# solar_collector_controller_V1_21.net
KiCad netlist of a schematic drawn in EAGLE
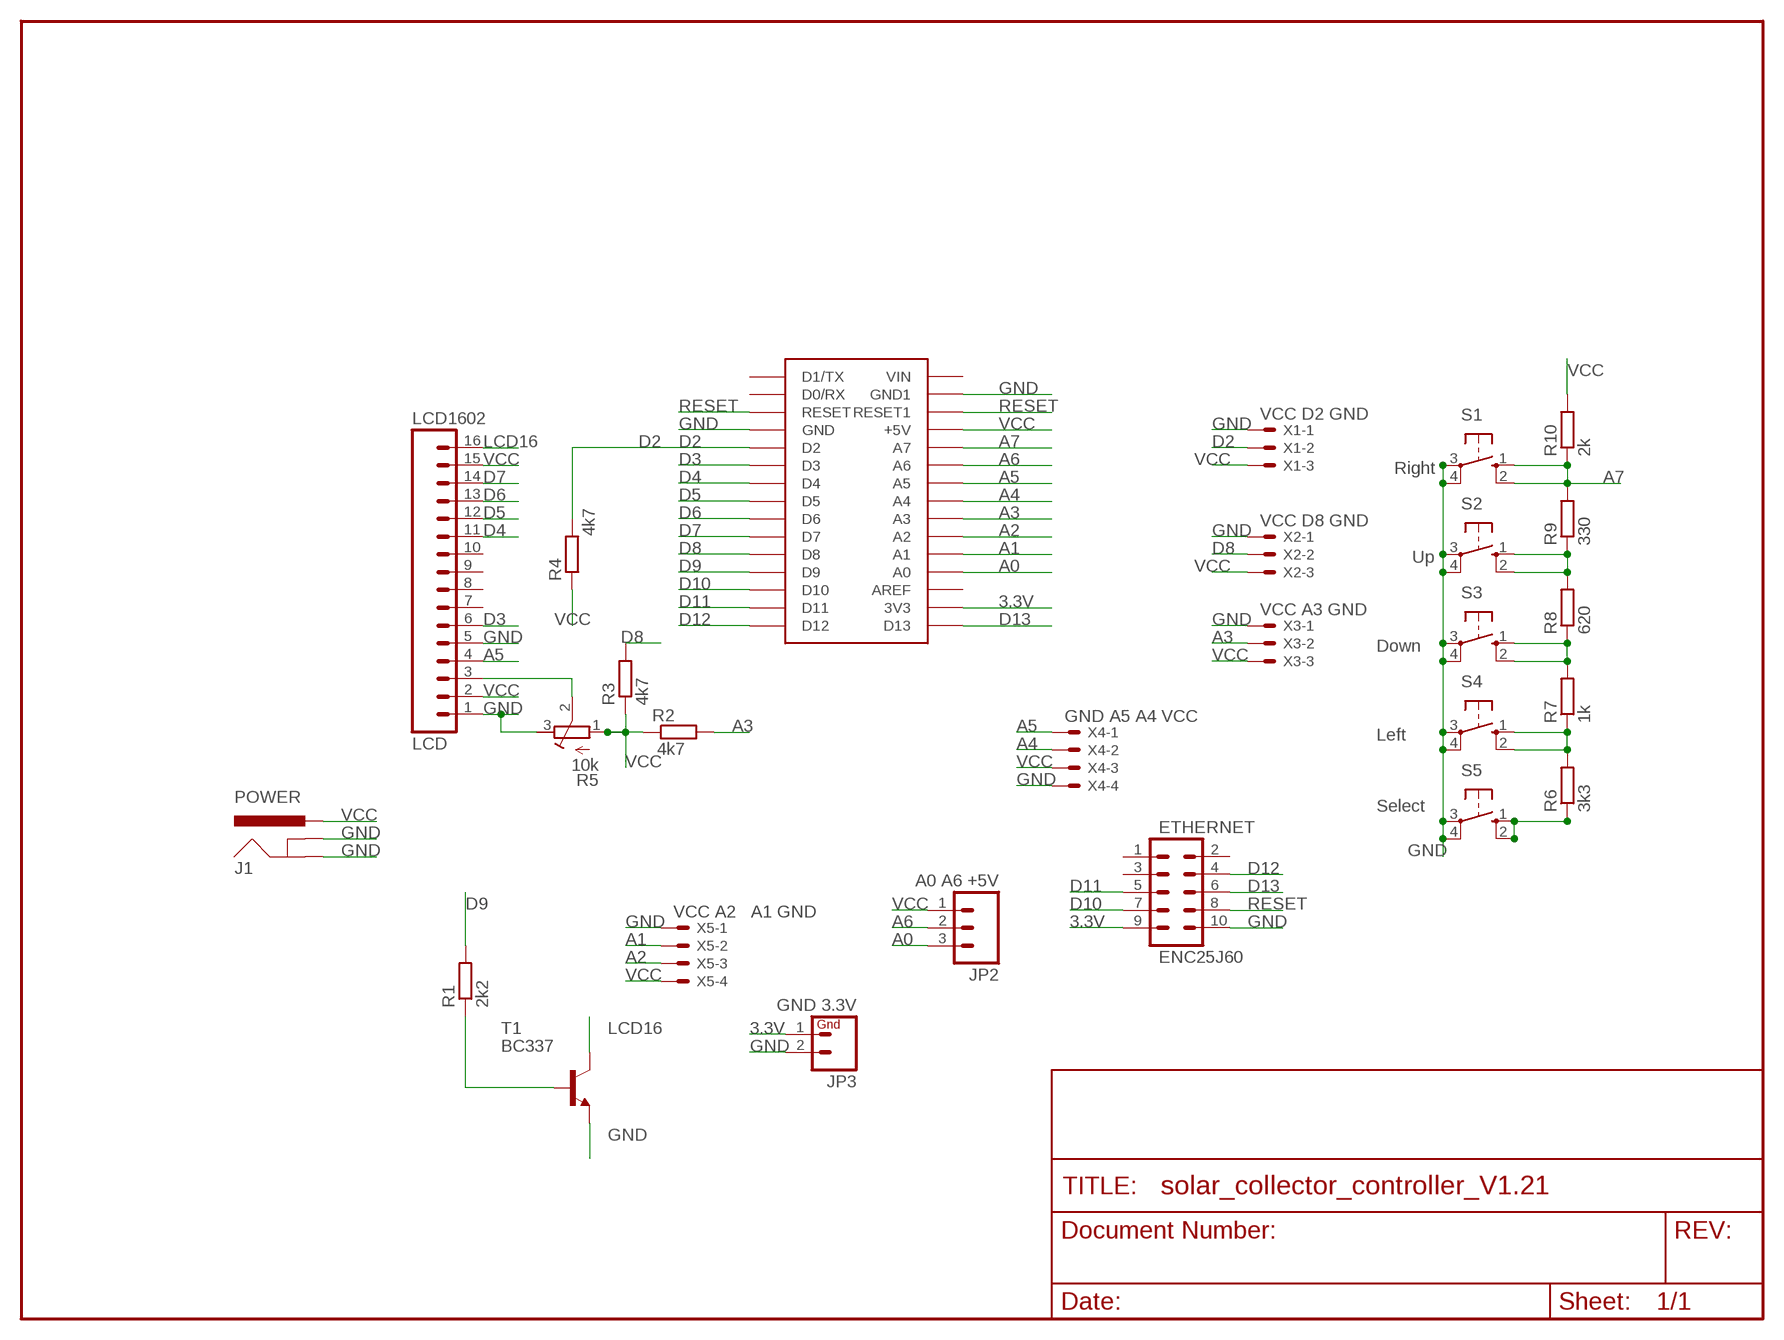
[diagram p0: schematic, sheet 1]

(export (version "E")
  (design (tool "Eeschema 10.0.6"))
  (components
    (comp (ref "ETHERNET")
      (value "ENC25J60")
      (footprint "eagle-import:AVR_ICSP")
      (libsource (lib "eagle-import") (part "M05X2PTH"))
    )
    (comp (ref "J1")
      (value "POWER")
      (footprint "eagle-import:POWER_JACK_PTH_LOCK")
      (libsource (lib "eagle-import") (part "POWER_JACKPTH_LOCK"))
    )
    (comp (ref "JP2")
      (value "A0 A6 +5V")
      (footprint "eagle-import:1X03")
      (libsource (lib "eagle-import") (part "M03PTH"))
    )
    (comp (ref "JP3")
      (value "GND 3.3V")
      (footprint "eagle-import:1X02")
      (libsource (lib "eagle-import") (part "M02PTH"))
    )
    (comp (ref "LCD1602")
      (value "LCD")
      (footprint "eagle-import:16P-2.54")
      (libsource (lib "eagle-import") (part "HEADER-16P-2.54"))
    )
    (comp (ref "R1")
      (value "2k2")
      (footprint "eagle-import:0207_10")
      (libsource (lib "eagle-import") (part "R-EU_0207/10"))
    )
    (comp (ref "R2")
      (value "4k7")
      (footprint "eagle-import:0207_10")
      (libsource (lib "eagle-import") (part "R-EU_0207/10"))
    )
    (comp (ref "R3")
      (value "4k7")
      (footprint "eagle-import:0207_10")
      (libsource (lib "eagle-import") (part "R-EU_0207/10"))
    )
    (comp (ref "R4")
      (value "4k7")
      (footprint "eagle-import:0207_10")
      (libsource (lib "eagle-import") (part "R-EU_0207/10"))
    )
    (comp (ref "R5")
      (value "10k")
      (footprint "eagle-import:RTRIM64W")
      (libsource (lib "eagle-import") (part "R-TRIMM64W"))
    )
    (comp (ref "R6")
      (value "3k3")
      (footprint "eagle-import:0207_10")
      (libsource (lib "eagle-import") (part "R-EU_0207/10"))
    )
    (comp (ref "R7")
      (value "1k")
      (footprint "eagle-import:0207_10")
      (libsource (lib "eagle-import") (part "R-EU_0207/10"))
    )
    (comp (ref "R8")
      (value "620")
      (footprint "eagle-import:0207_10")
      (libsource (lib "eagle-import") (part "R-EU_0207/10"))
    )
    (comp (ref "R9")
      (value "330")
      (footprint "eagle-import:0207_10")
      (libsource (lib "eagle-import") (part "R-EU_0207/10"))
    )
    (comp (ref "R10")
      (value "2k")
      (footprint "eagle-import:0207_10")
      (libsource (lib "eagle-import") (part "R-EU_0207/10"))
    )
    (comp (ref "S1")
      (value "Right")
      (footprint "eagle-import:B3F-10XX")
      (fields (field (name "MPN") "B3F-1000"))
      (libsource (lib "eagle-import") (part "10-XX"))
    )
    (comp (ref "S2")
      (value "Up")
      (footprint "eagle-import:B3F-10XX")
      (fields (field (name "MPN") "B3F-1000"))
      (libsource (lib "eagle-import") (part "10-XX"))
    )
    (comp (ref "S3")
      (value "Down")
      (footprint "eagle-import:B3F-10XX")
      (fields (field (name "MPN") "B3F-1000"))
      (libsource (lib "eagle-import") (part "10-XX"))
    )
    (comp (ref "S4")
      (value "Left")
      (footprint "eagle-import:B3F-10XX")
      (fields (field (name "MPN") "B3F-1000"))
      (libsource (lib "eagle-import") (part "10-XX"))
    )
    (comp (ref "S5")
      (value "Select")
      (footprint "eagle-import:B3F-10XX")
      (fields (field (name "MPN") "B3F-1000"))
      (libsource (lib "eagle-import") (part "10-XX"))
    )
    (comp (ref "T1")
      (value "BC337")
      (footprint "eagle-import:TO92")
      (libsource (lib "eagle-import") (part "BC337"))
    )
    (comp (ref "U$2")
      (value "ARDUINONANO")
      (footprint "eagle-import:PDIP-32")
      (libsource (lib "eagle-import") (part "ARDUINONANO"))
    )
    (comp (ref "X1")
      (value "VCC D2 GND")
      (footprint "eagle-import:22-23-2031")
      (fields (field (name "MF") "MOLEX") (field (name "MPN") "22-23-2031"))
      (libsource (lib "eagle-import") (part "22-23-2031"))
    )
    (comp (ref "X2")
      (value "VCC D8 GND")
      (footprint "eagle-import:22-23-2031")
      (fields (field (name "MF") "MOLEX") (field (name "MPN") "22-23-2031"))
      (libsource (lib "eagle-import") (part "22-23-2031"))
    )
    (comp (ref "X3")
      (value "VCC A3 GND")
      (footprint "eagle-import:22-23-2031")
      (fields (field (name "MF") "MOLEX") (field (name "MPN") "22-23-2031"))
      (libsource (lib "eagle-import") (part "22-23-2031"))
    )
    (comp (ref "X4")
      (value "GND A5 A4 VCC")
      (footprint "eagle-import:22-23-2041")
      (fields (field (name "MF") "MOLEX") (field (name "MPN") "22-23-2041"))
      (libsource (lib "eagle-import") (part "22-23-2041"))
    )
    (comp (ref "X5")
      (value "VCC A2 A1 GND")
      (footprint "eagle-import:22-23-2041")
      (fields (field (name "MF") "MOLEX") (field (name "MPN") "22-23-2041"))
      (libsource (lib "eagle-import") (part "22-23-2041"))
    )
  )
  (nets
    (net (code "1") (name "/3.3V") (class "Default")
      (node (ref "ETHERNET") (pin "9") (pinfunction "9_9") (pintype "passive"))
      (node (ref "JP3") (pin "1") (pinfunction "1_1") (pintype "passive"))
      (node (ref "U$2") (pin "3V3") (pinfunction "3V3_3V3") (pintype "bidirectional"))
    )
    (net (code "2") (name "/A0") (class "Default")
      (node (ref "JP2") (pin "3") (pinfunction "3_3") (pintype "passive"))
      (node (ref "U$2") (pin "A0") (pinfunction "A0_A0") (pintype "bidirectional"))
    )
    (net (code "3") (name "/A1") (class "Default")
      (node (ref "U$2") (pin "A1") (pinfunction "A1_A1") (pintype "bidirectional"))
      (node (ref "X5") (pin "2") (pinfunction "S_2") (pintype "passive"))
    )
    (net (code "4") (name "/A2") (class "Default")
      (node (ref "U$2") (pin "A2") (pinfunction "A2_A2") (pintype "bidirectional"))
      (node (ref "X5") (pin "3") (pinfunction "S_3") (pintype "passive"))
    )
    (net (code "5") (name "/A3") (class "Default")
      (node (ref "R2") (pin "2") (pinfunction "2_2") (pintype "passive"))
      (node (ref "U$2") (pin "A3") (pinfunction "A3_A3") (pintype "bidirectional"))
      (node (ref "X3") (pin "2") (pinfunction "S_2") (pintype "passive"))
    )
    (net (code "6") (name "/A4") (class "Default")
      (node (ref "U$2") (pin "A4") (pinfunction "A4_A4") (pintype "bidirectional"))
      (node (ref "X4") (pin "2") (pinfunction "S_2") (pintype "passive"))
    )
    (net (code "7") (name "/A5") (class "Default")
      (node (ref "LCD1602") (pin "4") (pinfunction "4_4") (pintype "passive"))
      (node (ref "U$2") (pin "A5") (pinfunction "A5_A5") (pintype "bidirectional"))
      (node (ref "X4") (pin "1") (pinfunction "S_1") (pintype "passive"))
    )
    (net (code "8") (name "/A6") (class "Default")
      (node (ref "JP2") (pin "2") (pinfunction "2_2") (pintype "passive"))
      (node (ref "U$2") (pin "A6") (pinfunction "A6_A6") (pintype "bidirectional"))
    )
    (net (code "9") (name "/A7") (class "Default")
      (node (ref "R10") (pin "1") (pinfunction "1_1") (pintype "passive"))
      (node (ref "R9") (pin "2") (pinfunction "2_2") (pintype "passive"))
      (node (ref "S1") (pin "1") (pinfunction "S_1") (pintype "passive"))
      (node (ref "S1") (pin "2") (pinfunction "S1_2") (pintype "passive"))
      (node (ref "U$2") (pin "A7") (pinfunction "A7_A7") (pintype "bidirectional"))
    )
    (net (code "10") (name "/D2") (class "Default")
      (node (ref "R4") (pin "2") (pinfunction "2_2") (pintype "passive"))
      (node (ref "U$2") (pin "D2") (pinfunction "D2_D2") (pintype "bidirectional"))
      (node (ref "X1") (pin "2") (pinfunction "S_2") (pintype "passive"))
    )
    (net (code "11") (name "/D3") (class "Default")
      (node (ref "LCD1602") (pin "6") (pinfunction "6_6") (pintype "passive"))
      (node (ref "U$2") (pin "D3") (pinfunction "D3_D3") (pintype "bidirectional"))
    )
    (net (code "12") (name "/D4") (class "Default")
      (node (ref "LCD1602") (pin "11") (pinfunction "11_11") (pintype "passive"))
      (node (ref "U$2") (pin "D4") (pinfunction "D4_D4") (pintype "bidirectional"))
    )
    (net (code "13") (name "/D5") (class "Default")
      (node (ref "LCD1602") (pin "12") (pinfunction "12_12") (pintype "passive"))
      (node (ref "U$2") (pin "D5") (pinfunction "D5_D5") (pintype "bidirectional"))
    )
    (net (code "14") (name "/D6") (class "Default")
      (node (ref "LCD1602") (pin "13") (pinfunction "13_13") (pintype "passive"))
      (node (ref "U$2") (pin "D6") (pinfunction "D6_D6") (pintype "bidirectional"))
    )
    (net (code "15") (name "/D7") (class "Default")
      (node (ref "LCD1602") (pin "14") (pinfunction "14_14") (pintype "passive"))
      (node (ref "U$2") (pin "D7") (pinfunction "D7_D7") (pintype "bidirectional"))
    )
    (net (code "16") (name "/D8") (class "Default")
      (node (ref "R3") (pin "2") (pinfunction "2_2") (pintype "passive"))
      (node (ref "U$2") (pin "D8") (pinfunction "D8_D8") (pintype "bidirectional"))
      (node (ref "X2") (pin "2") (pinfunction "S_2") (pintype "passive"))
    )
    (net (code "17") (name "/D9") (class "Default")
      (node (ref "R1") (pin "2") (pinfunction "2_2") (pintype "passive"))
      (node (ref "U$2") (pin "D9") (pinfunction "D9_D9") (pintype "bidirectional"))
    )
    (net (code "18") (name "/D10") (class "Default")
      (node (ref "ETHERNET") (pin "7") (pinfunction "7_7") (pintype "passive"))
      (node (ref "U$2") (pin "D10") (pinfunction "D10_D10") (pintype "bidirectional"))
    )
    (net (code "19") (name "/D11") (class "Default")
      (node (ref "ETHERNET") (pin "5") (pinfunction "5_5") (pintype "passive"))
      (node (ref "U$2") (pin "D11") (pinfunction "D11_D11") (pintype "bidirectional"))
    )
    (net (code "20") (name "/D12") (class "Default")
      (node (ref "ETHERNET") (pin "4") (pinfunction "4_4") (pintype "passive"))
      (node (ref "U$2") (pin "D12") (pinfunction "D12_D12") (pintype "bidirectional"))
    )
    (net (code "21") (name "/D13") (class "Default")
      (node (ref "ETHERNET") (pin "6") (pinfunction "6_6") (pintype "passive"))
      (node (ref "U$2") (pin "D13") (pinfunction "D13_D13") (pintype "bidirectional"))
    )
    (net (code "22") (name "/GND") (class "Default")
      (node (ref "ETHERNET") (pin "10") (pinfunction "10_10") (pintype "passive"))
      (node (ref "J1") (pin "GND") (pinfunction "GND_GND") (pintype "bidirectional"))
      (node (ref "J1") (pin "GNDBREAK") (pinfunction "GNDBREAK_GNDBREAK") (pintype "bidirectional"))
      (node (ref "JP3") (pin "2") (pinfunction "2_2") (pintype "passive"))
      (node (ref "LCD1602") (pin "1") (pinfunction "1_1") (pintype "passive"))
      (node (ref "LCD1602") (pin "5") (pinfunction "5_5") (pintype "passive"))
      (node (ref "R5") (pin "3") (pinfunction "A_3") (pintype "passive"))
      (node (ref "S1") (pin "3") (pinfunction "P_3") (pintype "passive"))
      (node (ref "S1") (pin "4") (pinfunction "P1_4") (pintype "passive"))
      (node (ref "S2") (pin "3") (pinfunction "P_3") (pintype "passive"))
      (node (ref "S2") (pin "4") (pinfunction "P1_4") (pintype "passive"))
      (node (ref "S3") (pin "3") (pinfunction "P_3") (pintype "passive"))
      (node (ref "S3") (pin "4") (pinfunction "P1_4") (pintype "passive"))
      (node (ref "S4") (pin "3") (pinfunction "P_3") (pintype "passive"))
      (node (ref "S4") (pin "4") (pinfunction "P1_4") (pintype "passive"))
      (node (ref "S5") (pin "3") (pinfunction "P_3") (pintype "passive"))
      (node (ref "S5") (pin "4") (pinfunction "P1_4") (pintype "passive"))
      (node (ref "T1") (pin "1") (pinfunction "E_1") (pintype "passive"))
      (node (ref "U$2") (pin "GND") (pinfunction "GND_GND") (pintype "bidirectional"))
      (node (ref "U$2") (pin "GND1") (pinfunction "GND1_GND1") (pintype "bidirectional"))
      (node (ref "X1") (pin "1") (pinfunction "S_1") (pintype "passive"))
      (node (ref "X2") (pin "1") (pinfunction "S_1") (pintype "passive"))
      (node (ref "X3") (pin "1") (pinfunction "S_1") (pintype "passive"))
      (node (ref "X4") (pin "4") (pinfunction "S_4") (pintype "passive"))
      (node (ref "X5") (pin "1") (pinfunction "S_1") (pintype "passive"))
    )
    (net (code "23") (name "/LCD16") (class "Default")
      (node (ref "LCD1602") (pin "16") (pinfunction "16_16") (pintype "passive"))
      (node (ref "T1") (pin "3") (pinfunction "C_3") (pintype "passive"))
    )
    (net (code "24") (name "/RESET") (class "Default")
      (node (ref "ETHERNET") (pin "8") (pinfunction "8_8") (pintype "passive"))
      (node (ref "U$2") (pin "RESET") (pinfunction "RESET_RESET") (pintype "bidirectional"))
      (node (ref "U$2") (pin "RESET1") (pinfunction "RESET1_RESET1") (pintype "bidirectional"))
    )
    (net (code "25") (name "/VCC") (class "Default")
      (node (ref "J1") (pin "PWR") (pinfunction "PWR_PWR") (pintype "bidirectional"))
      (node (ref "JP2") (pin "1") (pinfunction "1_1") (pintype "passive"))
      (node (ref "LCD1602") (pin "15") (pinfunction "15_15") (pintype "passive"))
      (node (ref "LCD1602") (pin "2") (pinfunction "2_2") (pintype "passive"))
      (node (ref "R10") (pin "2") (pinfunction "2_2") (pintype "passive"))
      (node (ref "R2") (pin "1") (pinfunction "1_1") (pintype "passive"))
      (node (ref "R3") (pin "1") (pinfunction "1_1") (pintype "passive"))
      (node (ref "R4") (pin "1") (pinfunction "1_1") (pintype "passive"))
      (node (ref "R5") (pin "1") (pinfunction "E_1") (pintype "passive"))
      (node (ref "U$2") (pin "+5V") (pinfunction "+5V_+5V") (pintype "bidirectional"))
      (node (ref "X1") (pin "3") (pinfunction "S_3") (pintype "passive"))
      (node (ref "X2") (pin "3") (pinfunction "S_3") (pintype "passive"))
      (node (ref "X3") (pin "3") (pinfunction "S_3") (pintype "passive"))
      (node (ref "X4") (pin "3") (pinfunction "S_3") (pintype "passive"))
      (node (ref "X5") (pin "4") (pinfunction "S_4") (pintype "passive"))
    )
    (net (code "26") (name "Net-(R5-S)") (class "Default")
      (node (ref "LCD1602") (pin "3") (pinfunction "3_3") (pintype "passive"))
      (node (ref "R5") (pin "2") (pinfunction "S_2") (pintype "passive"))
    )
    (net (code "27") (name "Net-(S2-S)") (class "Default")
      (node (ref "R8") (pin "2") (pinfunction "2_2") (pintype "passive"))
      (node (ref "R9") (pin "1") (pinfunction "1_1") (pintype "passive"))
      (node (ref "S2") (pin "1") (pinfunction "S_1") (pintype "passive"))
      (node (ref "S2") (pin "2") (pinfunction "S1_2") (pintype "passive"))
    )
    (net (code "28") (name "Net-(S3-S)") (class "Default")
      (node (ref "R7") (pin "2") (pinfunction "2_2") (pintype "passive"))
      (node (ref "R8") (pin "1") (pinfunction "1_1") (pintype "passive"))
      (node (ref "S3") (pin "1") (pinfunction "S_1") (pintype "passive"))
      (node (ref "S3") (pin "2") (pinfunction "S1_2") (pintype "passive"))
    )
    (net (code "29") (name "Net-(S4-S)") (class "Default")
      (node (ref "R6") (pin "2") (pinfunction "2_2") (pintype "passive"))
      (node (ref "R7") (pin "1") (pinfunction "1_1") (pintype "passive"))
      (node (ref "S4") (pin "1") (pinfunction "S_1") (pintype "passive"))
      (node (ref "S4") (pin "2") (pinfunction "S1_2") (pintype "passive"))
    )
    (net (code "30") (name "Net-(S5-S)") (class "Default")
      (node (ref "R6") (pin "1") (pinfunction "1_1") (pintype "passive"))
      (node (ref "S5") (pin "1") (pinfunction "S_1") (pintype "passive"))
      (node (ref "S5") (pin "2") (pinfunction "S1_2") (pintype "passive"))
    )
    (net (code "31") (name "Net-(T1-B)") (class "Default")
      (node (ref "R1") (pin "1") (pinfunction "1_1") (pintype "passive"))
      (node (ref "T1") (pin "2") (pinfunction "B_2") (pintype "passive"))
    )
    (net (code "32") (name "unconnected-(ETHERNET-Pad1)") (class "Default")
      (node (ref "ETHERNET") (pin "1") (pinfunction "1_1") (pintype "passive"))
    )
    (net (code "33") (name "unconnected-(ETHERNET-Pad2)") (class "Default")
      (node (ref "ETHERNET") (pin "2") (pinfunction "2_2") (pintype "passive"))
    )
    (net (code "34") (name "unconnected-(ETHERNET-Pad3)") (class "Default")
      (node (ref "ETHERNET") (pin "3") (pinfunction "3_3") (pintype "passive"))
    )
    (net (code "35") (name "unconnected-(LCD1602-Pad7)") (class "Default")
      (node (ref "LCD1602") (pin "7") (pinfunction "7_7") (pintype "passive"))
    )
    (net (code "36") (name "unconnected-(LCD1602-Pad8)") (class "Default")
      (node (ref "LCD1602") (pin "8") (pinfunction "8_8") (pintype "passive"))
    )
    (net (code "37") (name "unconnected-(LCD1602-Pad9)") (class "Default")
      (node (ref "LCD1602") (pin "9") (pinfunction "9_9") (pintype "passive"))
    )
    (net (code "38") (name "unconnected-(LCD1602-Pad10)") (class "Default")
      (node (ref "LCD1602") (pin "10") (pinfunction "10_10") (pintype "passive"))
    )
    (net (code "39") (name "unconnected-(U$2-PadAREF)") (class "Default")
      (node (ref "U$2") (pin "AREF") (pinfunction "AREF_AREF") (pintype "bidirectional"))
    )
    (net (code "40") (name "unconnected-(U$2-PadD0{slash}RX)") (class "Default")
      (node (ref "U$2") (pin "D0/RX") (pinfunction "D0/RX_D0/RX") (pintype "bidirectional"))
    )
    (net (code "41") (name "unconnected-(U$2-PadD1{slash}TX)") (class "Default")
      (node (ref "U$2") (pin "D1/TX") (pinfunction "D1/TX_D1/TX") (pintype "bidirectional"))
    )
    (net (code "42") (name "unconnected-(U$2-PadVIN)") (class "Default")
      (node (ref "U$2") (pin "VIN") (pinfunction "VIN_VIN") (pintype "bidirectional"))
    )
  )
)
